# power.net
KiCad netlist of a schematic drawn in Altium Designer
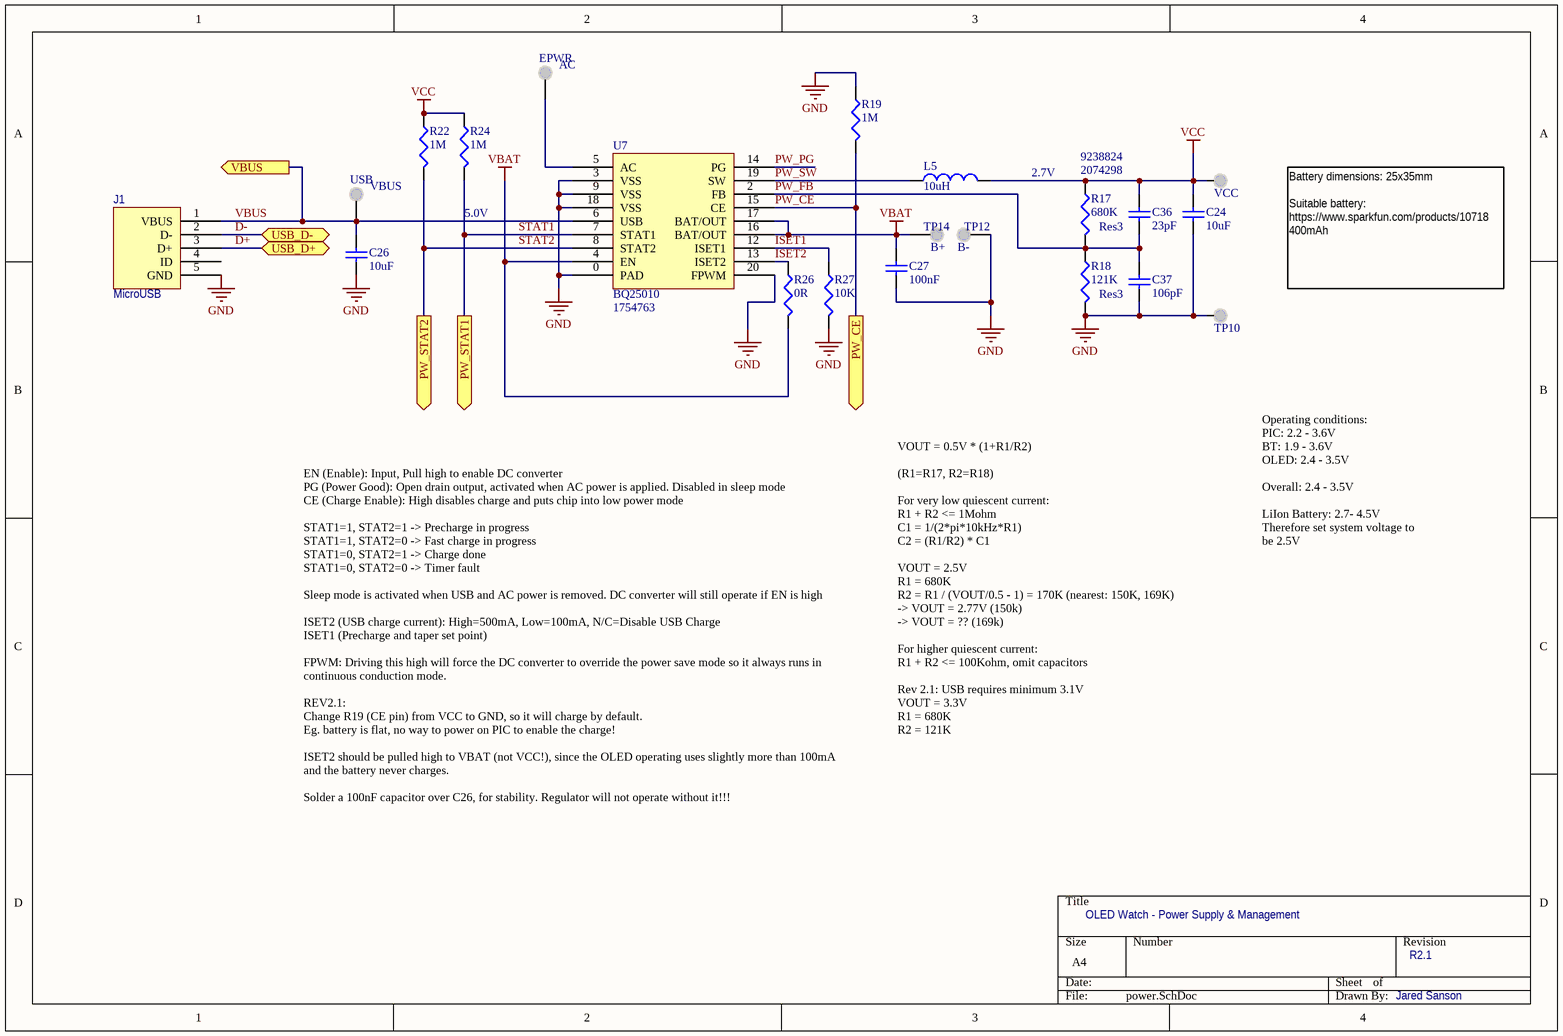
[diagram p0: power.SchDoc]

(export (version "E")
  (design (tool "Eeschema 10.0.6"))
  (components
    (comp (ref "C24")
      (value "10uF")
      (footprint "0805C")
      (description "Capacitor")
      (fields (field (name "Comment") "Cap") (field (name "PUBLISHER") "Altium Limited"))
      (libsource (lib "Miscellaneous Devices") (part "Cap"))
    )
    (comp (ref "C26")
      (value "10uF")
      (footprint "0805C")
      (description "Capacitor")
      (fields (field (name "Comment") "Cap") (field (name "PUBLISHER") "Altium Limited"))
      (libsource (lib "Miscellaneous Devices") (part "Cap"))
    )
    (comp (ref "C27")
      (value "100nF")
      (footprint "0603C")
      (description "Capacitor")
      (fields (field (name "Comment") "Cap") (field (name "PUBLISHER") "Altium Limited"))
      (libsource (lib "Miscellaneous Devices") (part "Cap"))
    )
    (comp (ref "C36")
      (value "23pF")
      (footprint "0603C")
      (description "Capacitor")
      (fields (field (name "Comment") "Cap") (field (name "PUBLISHER") "Altium Limited"))
      (libsource (lib "Miscellaneous Devices") (part "Cap"))
    )
    (comp (ref "C37")
      (value "106pF")
      (footprint "0603C")
      (description "Capacitor")
      (fields (field (name "Comment") "Cap") (field (name "PUBLISHER") "Altium Limited"))
      (libsource (lib "Miscellaneous Devices") (part "Cap"))
    )
    (comp (ref "EPWR")
      (value "AC")
      (footprint "TESTPOINT_TOP")
      (description "Test Point")
      (libsource (lib "JLib") (part "TestPoint"))
    )
    (comp (ref "J1") (value "MicroUSB") (footprint "MICRO_USB") (libsource (lib "JLib") (part "MicroUSB")))
    (comp (ref "L5")
      (value "10uH")
      (footprint "INDC3225N")
      (description "Inductor")
      (fields (field (name "PUBLISHER") "Altium Limited"))
      (libsource (lib "Miscellaneous Devices") (part "Inductor"))
    )
    (comp (ref "R17")
      (value "Res3")
      (footprint "0603R")
      (description "Resistor")
      (fields
        (field (name "ALTIUM_VALUE") "680K")
        (field (name "SUPPLIER PART NUMBER 1") "2074298")
        (field (name "SUPPLIER PART NUMBER 2") "9238824")
        (field (name "PUBLISHER") "Altium Limited")
      )
      (libsource (lib "Miscellaneous Devices") (part "Res3"))
    )
    (comp (ref "R18")
      (value "Res3")
      (footprint "0603R")
      (description "Resistor")
      (fields (field (name "ALTIUM_VALUE") "121K") (field (name "PUBLISHER") "Altium Limited"))
      (libsource (lib "Miscellaneous Devices") (part "Res3"))
    )
    (comp (ref "R19")
      (value "1M")
      (footprint "0603R")
      (description "Resistor")
      (fields (field (name "Comment") "Res3") (field (name "PUBLISHER") "Altium Limited"))
      (libsource (lib "Miscellaneous Devices") (part "Res3"))
    )
    (comp (ref "R22")
      (value "1M")
      (footprint "0603R")
      (description "Resistor")
      (fields (field (name "Comment") "Res3") (field (name "PUBLISHER") "Altium Limited"))
      (libsource (lib "Miscellaneous Devices") (part "Res3"))
    )
    (comp (ref "R24")
      (value "1M")
      (footprint "0603R")
      (description "Resistor")
      (fields (field (name "Comment") "Res3") (field (name "PUBLISHER") "Altium Limited"))
      (libsource (lib "Miscellaneous Devices") (part "Res3"))
    )
    (comp (ref "R26")
      (value "0R")
      (footprint "0603R")
      (description "Resistor")
      (fields (field (name "Comment") "Res3") (field (name "PUBLISHER") "Altium Limited"))
      (libsource (lib "Miscellaneous Devices") (part "Res3"))
    )
    (comp (ref "R27")
      (value "10K")
      (footprint "0603R")
      (description "Resistor")
      (fields (field (name "Comment") "Res3") (field (name "PUBLISHER") "Altium Limited"))
      (libsource (lib "Miscellaneous Devices") (part "Res3"))
    )
    (comp (ref "TP10")
      (value "GND")
      (footprint "TESTPOINT_TOP")
      (description "Test Point")
      (libsource (lib "JLib") (part "TestPoint"))
    )
    (comp (ref "TP12")
      (value "B-")
      (footprint "TESTPOINT_TOP")
      (description "Test Point")
      (libsource (lib "JLib") (part "TestPoint"))
    )
    (comp (ref "TP14")
      (value "B+")
      (footprint "TESTPOINT_TOP")
      (description "Test Point")
      (libsource (lib "JLib") (part "TestPoint"))
    )
    (comp (ref "U7")
      (value "BQ25010")
      (footprint "RHL")
      (fields (field (name "SUPPLIER PART NUMBER 1") "1754763"))
      (libsource (lib "JLib") (part "BQ25010"))
    )
    (comp (ref "USB")
      (value "VBUS")
      (footprint "TESTPOINT_TOP")
      (description "Test Point")
      (libsource (lib "JLib") (part "TestPoint"))
    )
    (comp (ref "VCC")
      (value "VCC")
      (footprint "TESTPOINT_TOP")
      (description "Test Point")
      (libsource (lib "JLib") (part "TestPoint"))
    )
  )
  (nets
    (net (code "1") (name "/D+") (class "Default")
      (node (ref "J1") (pin "3") (pinfunction "D+_3") (pintype "passive"))
    )
    (net (code "2") (name "/D-") (class "Default")
      (node (ref "J1") (pin "2") (pinfunction "D-_2") (pintype "passive"))
    )
    (net (code "3") (name "/ISET1") (class "Default")
      (node (ref "R27") (pin "1") (pinfunction "1_1") (pintype "passive"))
      (node (ref "U7") (pin "12") (pinfunction "ISET1_12") (pintype "passive"))
    )
    (net (code "4") (name "/ISET2") (class "Default")
      (node (ref "R26") (pin "1") (pinfunction "1_1") (pintype "passive"))
      (node (ref "U7") (pin "13") (pinfunction "ISET2_13") (pintype "passive"))
    )
    (net (code "5") (name "/PW_CE") (class "Default")
      (node (ref "R19") (pin "2") (pinfunction "2_2") (pintype "passive"))
      (node (ref "U7") (pin "15") (pinfunction "CE_15") (pintype "passive"))
    )
    (net (code "6") (name "/PW_FB") (class "Default")
      (node (ref "C36") (pin "2") (pinfunction "2_2") (pintype "passive"))
      (node (ref "C37") (pin "1") (pinfunction "1_1") (pintype "passive"))
      (node (ref "R17") (pin "2") (pinfunction "2_2") (pintype "passive"))
      (node (ref "R18") (pin "1") (pinfunction "1_1") (pintype "passive"))
      (node (ref "U7") (pin "2") (pinfunction "FB_2") (pintype "passive"))
    )
    (net (code "7") (name "/PW_PG") (class "Default")
      (node (ref "U7") (pin "14") (pinfunction "PG_14") (pintype "passive"))
    )
    (net (code "8") (name "/PW_SW") (class "Default")
      (node (ref "L5") (pin "1") (pinfunction "1_1") (pintype "passive"))
      (node (ref "U7") (pin "19") (pinfunction "SW_19") (pintype "passive"))
    )
    (net (code "9") (name "/STAT1") (class "Default")
      (node (ref "R24") (pin "2") (pinfunction "2_2") (pintype "passive"))
      (node (ref "U7") (pin "7") (pinfunction "STAT1_7") (pintype "passive"))
    )
    (net (code "10") (name "/STAT2") (class "Default")
      (node (ref "R22") (pin "2") (pinfunction "2_2") (pintype "passive"))
      (node (ref "U7") (pin "8") (pinfunction "STAT2_8") (pintype "passive"))
    )
    (net (code "11") (name "/VBUS") (class "Default")
      (node (ref "C26") (pin "1") (pinfunction "1_1") (pintype "passive"))
      (node (ref "J1") (pin "1") (pinfunction "VBUS_1") (pintype "passive"))
      (node (ref "U7") (pin "6") (pinfunction "USB_6") (pintype "passive"))
      (node (ref "USB") (pin "1") (pinfunction "TP_1") (pintype "passive"))
    )
    (net (code "12") (name "GND") (class "Default")
      (node (ref "C24") (pin "2") (pinfunction "2_2") (pintype "passive"))
      (node (ref "C26") (pin "2") (pinfunction "2_2") (pintype "passive"))
      (node (ref "C27") (pin "2") (pinfunction "2_2") (pintype "passive"))
      (node (ref "C37") (pin "2") (pinfunction "2_2") (pintype "passive"))
      (node (ref "J1") (pin "5") (pinfunction "GND_5") (pintype "passive"))
      (node (ref "R18") (pin "2") (pinfunction "2_2") (pintype "passive"))
      (node (ref "R19") (pin "1") (pinfunction "1_1") (pintype "passive"))
      (node (ref "R27") (pin "2") (pinfunction "2_2") (pintype "passive"))
      (node (ref "TP10") (pin "1") (pinfunction "TP_1") (pintype "passive"))
      (node (ref "TP12") (pin "1") (pinfunction "TP_1") (pintype "passive"))
      (node (ref "U7") (pin "0") (pinfunction "PAD_0") (pintype "passive"))
      (node (ref "U7") (pin "18") (pinfunction "VSS_18") (pintype "passive"))
      (node (ref "U7") (pin "20") (pinfunction "FPWM_20") (pintype "passive"))
      (node (ref "U7") (pin "3") (pinfunction "VSS_3") (pintype "passive"))
      (node (ref "U7") (pin "9") (pinfunction "VSS_9") (pintype "passive"))
    )
    (net (code "13") (name "Net-(EPWR-TP)") (class "Default")
      (node (ref "EPWR") (pin "1") (pinfunction "TP_1") (pintype "passive"))
      (node (ref "U7") (pin "5") (pinfunction "AC_5") (pintype "passive"))
    )
    (net (code "14") (name "VBAT") (class "Default")
      (node (ref "C27") (pin "1") (pinfunction "1_1") (pintype "passive"))
      (node (ref "R26") (pin "2") (pinfunction "2_2") (pintype "passive"))
      (node (ref "TP14") (pin "1") (pinfunction "TP_1") (pintype "passive"))
      (node (ref "U7") (pin "16") (pinfunction "BAT/OUT_16") (pintype "passive"))
      (node (ref "U7") (pin "17") (pinfunction "BAT/OUT_17") (pintype "passive"))
      (node (ref "U7") (pin "4") (pinfunction "EN_4") (pintype "passive"))
    )
    (net (code "15") (name "VCC") (class "Default")
      (node (ref "C24") (pin "1") (pinfunction "1_1") (pintype "passive"))
      (node (ref "C36") (pin "1") (pinfunction "1_1") (pintype "passive"))
      (node (ref "L5") (pin "2") (pinfunction "2_2") (pintype "passive"))
      (node (ref "R17") (pin "1") (pinfunction "1_1") (pintype "passive"))
      (node (ref "R22") (pin "1") (pinfunction "1_1") (pintype "passive"))
      (node (ref "R24") (pin "1") (pinfunction "1_1") (pintype "passive"))
      (node (ref "VCC") (pin "1") (pinfunction "TP_1") (pintype "passive"))
    )
    (net (code "16") (name "unconnected-(J1-ID-Pad4)") (class "Default")
      (node (ref "J1") (pin "4") (pinfunction "ID_4") (pintype "passive"))
    )
  )
)
